# Custom_IMU_testing.net
KiCad netlist of a schematic drawn in Altium Designer
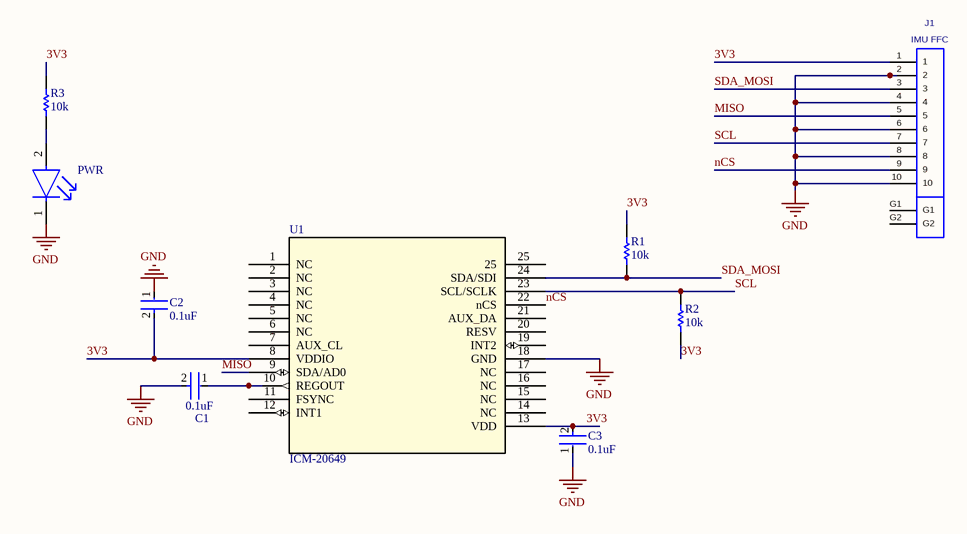
[diagram p0: Custom_IMU_testing.SchDoc]

(export (version "E")
  (design (tool "Eeschema 10.0.6"))
  (components
    (comp (ref "C1")
      (value "0.1uF")
      (footprint "FP-GRM15-MFG")
      (description "CAP CER 0.1UF 16V X7R 0402")
      (fields (field (name "MANUFACTURER PART NUMBER") "GRM155R71C104KA88D") (field (name "TOLERANCE") "10%"))
      (libsource (lib "Altium Content Vault") (part "236180d848d6139a670b325ea6854c9"))
    )
    (comp (ref "C2")
      (value "0.1uF")
      (footprint "FP-GRM15-MFG")
      (description "CAP CER 0.1UF 16V X7R 0402")
      (fields (field (name "MANUFACTURER PART NUMBER") "GRM155R71C104KA88D") (field (name "TOLERANCE") "10%"))
      (libsource (lib "Altium Content Vault") (part "236180d848d6139a670b325ea6854c9"))
    )
    (comp (ref "C3")
      (value "0.1uF")
      (footprint "FP-GRM15-MFG")
      (description "CAP CER 0.1UF 16V X7R 0402")
      (fields (field (name "MANUFACTURER PART NUMBER") "GRM155R71C104KA88D") (field (name "TOLERANCE") "10%"))
      (libsource (lib "Altium Content Vault") (part "236180d848d6139a670b325ea6854c9"))
    )
    (comp (ref "J1")
      (value "IMU FFC")
      (footprint "ZF5S-10-01-X-WT")
      (description "ZERO INSERTION FORCE 0.5MM ASSEMBLY, 01 LEAD STYLE.")
      (fields (field (name "MANUFACTURER") "SAMTEC") (field (name "CREATED") "January 30, 2015 - Wendy Xin"))
      (libsource (lib "Samtech 10 pin FFC connector") (part "ZF5S-10-01-X-WT"))
    )
    (comp (ref "PWR")
      (value "LTST-C190GKT")
      (footprint "FP-LTST-C190GKT-MFG")
      (description "LED GREEN CLEAR CHIP SMD")
      (fields (field (name "VOLTAGE") "2V"))
      (libsource (lib "Altium Content Vault") (part "8706943c75ba83719d021d2fdc84c58"))
    )
    (comp (ref "R1")
      (value "10k")
      (footprint "RESC1005X40X25LL05T10")
      (fields (field (name "PART NUMBER") "RC0402FR-0710KL") (field (name "MANUFACTURER") "Yageo / Phycomp"))
      (libsource (lib "Altium Content Vault") (part "RES"))
    )
    (comp (ref "R2")
      (value "10k")
      (footprint "RESC1005X40X25LL05T10")
      (fields (field (name "PART NUMBER") "RC0402FR-0710KL") (field (name "MANUFACTURER") "Yageo / Phycomp"))
      (libsource (lib "Altium Content Vault") (part "RES"))
    )
    (comp (ref "R3")
      (value "10k")
      (footprint "RESC1005X40X25LL05T10")
      (fields (field (name "PART NUMBER") "RC0402FR-0710KL") (field (name "MANUFACTURER") "Yageo / Phycomp"))
      (libsource (lib "Altium Content Vault") (part "RES"))
    )
    (comp (ref "U1")
      (value "ICM-20649")
      (footprint "QFN24_3X3X0P9_IVS")
      (description "No Description Available")
      (fields (field (name "COPYRIGHT") "Copyright (C) 2023 Ultra Librarian. All rights reserved."))
      (libsource (lib "ICM-20649") (part "ICM-20649"))
    )
  )
  (nets
    (net (code "1") (name "/3V3") (class "Default")
      (node (ref "C2") (pin "2") (pinfunction "2_2") (pintype "passive"))
      (node (ref "C3") (pin "2") (pinfunction "2_2") (pintype "passive"))
      (node (ref "J1") (pin "1") (pinfunction "1_1") (pintype "passive"))
      (node (ref "R1") (pin "2") (pinfunction "2_2") (pintype "passive"))
      (node (ref "R2") (pin "1") (pinfunction "1_1") (pintype "passive"))
      (node (ref "R3") (pin "2") (pinfunction "2_2") (pintype "passive"))
      (node (ref "U1") (pin "13") (pinfunction "VDD_13") (pintype "power_in"))
      (node (ref "U1") (pin "8") (pinfunction "VDDIO_8") (pintype "power_in"))
    )
    (net (code "2") (name "/MISO") (class "Default")
      (node (ref "J1") (pin "5") (pinfunction "5_5") (pintype "passive"))
      (node (ref "U1") (pin "9") (pinfunction "SDA/AD0_9") (pintype "bidirectional"))
    )
    (net (code "3") (name "/SCL") (class "Default")
      (node (ref "J1") (pin "7") (pinfunction "7_7") (pintype "passive"))
      (node (ref "R2") (pin "2") (pinfunction "2_2") (pintype "passive"))
      (node (ref "U1") (pin "23") (pinfunction "SCL/SCLK_23") (pintype "passive"))
    )
    (net (code "4") (name "/SDA_MOSI") (class "Default")
      (node (ref "J1") (pin "3") (pinfunction "3_3") (pintype "passive"))
      (node (ref "R1") (pin "1") (pinfunction "1_1") (pintype "passive"))
      (node (ref "U1") (pin "24") (pinfunction "SDA/SDI_24") (pintype "passive"))
    )
    (net (code "5") (name "/nCS") (class "Default")
      (node (ref "J1") (pin "9") (pinfunction "9_9") (pintype "passive"))
      (node (ref "U1") (pin "22") (pinfunction "nCS_22") (pintype "passive"))
    )
    (net (code "6") (name "GND") (class "Default")
      (node (ref "C1") (pin "2") (pinfunction "2_2") (pintype "passive"))
      (node (ref "C2") (pin "1") (pinfunction "1_1") (pintype "passive"))
      (node (ref "C3") (pin "1") (pinfunction "1_1") (pintype "passive"))
      (node (ref "J1") (pin "10") (pinfunction "10_10") (pintype "passive"))
      (node (ref "J1") (pin "2") (pinfunction "2_2") (pintype "passive"))
      (node (ref "J1") (pin "4") (pinfunction "4_4") (pintype "passive"))
      (node (ref "J1") (pin "6") (pinfunction "6_6") (pintype "passive"))
      (node (ref "J1") (pin "8") (pinfunction "8_8") (pintype "passive"))
      (node (ref "PWR") (pin "1") (pinfunction "C_1") (pintype "passive"))
      (node (ref "U1") (pin "18") (pinfunction "GND_18") (pintype "passive"))
    )
    (net (code "7") (name "Net-(PWR-A)") (class "Default")
      (node (ref "PWR") (pin "2") (pinfunction "A_2") (pintype "passive"))
      (node (ref "R3") (pin "1") (pinfunction "1_1") (pintype "passive"))
    )
    (net (code "8") (name "Net-(U1-REGOUT)") (class "Default")
      (node (ref "C1") (pin "1") (pinfunction "1_1") (pintype "passive"))
      (node (ref "U1") (pin "10") (pinfunction "REGOUT_10") (pintype "output"))
    )
    (net (code "9") (name "unconnected-(J1-PadG1)") (class "Default")
      (node (ref "J1") (pin "G1") (pinfunction "G1_G1") (pintype "passive"))
    )
    (net (code "10") (name "unconnected-(J1-PadG2)") (class "Default")
      (node (ref "J1") (pin "G2") (pinfunction "G2_G2") (pintype "passive"))
    )
    (net (code "11") (name "unconnected-(U1-AUX_CL-Pad7)") (class "Default")
      (node (ref "U1") (pin "7") (pinfunction "AUX_CL_7") (pintype "passive"))
    )
    (net (code "12") (name "unconnected-(U1-AUX_DA-Pad21)") (class "Default")
      (node (ref "U1") (pin "21") (pinfunction "AUX_DA_21") (pintype "passive"))
    )
    (net (code "13") (name "unconnected-(U1-FSYNC-Pad11)") (class "Default")
      (node (ref "U1") (pin "11") (pinfunction "FSYNC_11") (pintype "passive"))
    )
    (net (code "14") (name "unconnected-(U1-INT1-Pad12)") (class "Default")
      (node (ref "U1") (pin "12") (pinfunction "INT1_12") (pintype "bidirectional"))
    )
    (net (code "15") (name "unconnected-(U1-INT2-Pad19)") (class "Default")
      (node (ref "U1") (pin "19") (pinfunction "INT2_19") (pintype "bidirectional"))
    )
    (net (code "16") (name "unconnected-(U1-NC-Pad1)") (class "Default")
      (node (ref "U1") (pin "1") (pinfunction "NC_1") (pintype "passive"))
    )
    (net (code "17") (name "unconnected-(U1-NC-Pad2)") (class "Default")
      (node (ref "U1") (pin "2") (pinfunction "NC_2") (pintype "passive"))
    )
    (net (code "18") (name "unconnected-(U1-NC-Pad3)") (class "Default")
      (node (ref "U1") (pin "3") (pinfunction "NC_3") (pintype "passive"))
    )
    (net (code "19") (name "unconnected-(U1-NC-Pad4)") (class "Default")
      (node (ref "U1") (pin "4") (pinfunction "NC_4") (pintype "passive"))
    )
    (net (code "20") (name "unconnected-(U1-NC-Pad5)") (class "Default")
      (node (ref "U1") (pin "5") (pinfunction "NC_5") (pintype "passive"))
    )
    (net (code "21") (name "unconnected-(U1-NC-Pad6)") (class "Default")
      (node (ref "U1") (pin "6") (pinfunction "NC_6") (pintype "passive"))
    )
    (net (code "22") (name "unconnected-(U1-NC-Pad14)") (class "Default")
      (node (ref "U1") (pin "14") (pinfunction "NC_14") (pintype "passive"))
    )
    (net (code "23") (name "unconnected-(U1-NC-Pad15)") (class "Default")
      (node (ref "U1") (pin "15") (pinfunction "NC_15") (pintype "passive"))
    )
    (net (code "24") (name "unconnected-(U1-NC-Pad16)") (class "Default")
      (node (ref "U1") (pin "16") (pinfunction "NC_16") (pintype "passive"))
    )
    (net (code "25") (name "unconnected-(U1-NC-Pad17)") (class "Default")
      (node (ref "U1") (pin "17") (pinfunction "NC_17") (pintype "passive"))
    )
    (net (code "26") (name "unconnected-(U1-Pad25)") (class "Default")
      (node (ref "U1") (pin "25") (pinfunction "25_25") (pintype "passive"))
    )
    (net (code "27") (name "unconnected-(U1-RESV-Pad20)") (class "Default")
      (node (ref "U1") (pin "20") (pinfunction "RESV_20") (pintype "passive"))
    )
  )
)
